# COEXPIX_connectors_schematics.net
KiCad netlist of a schematic drawn in Altium Designer
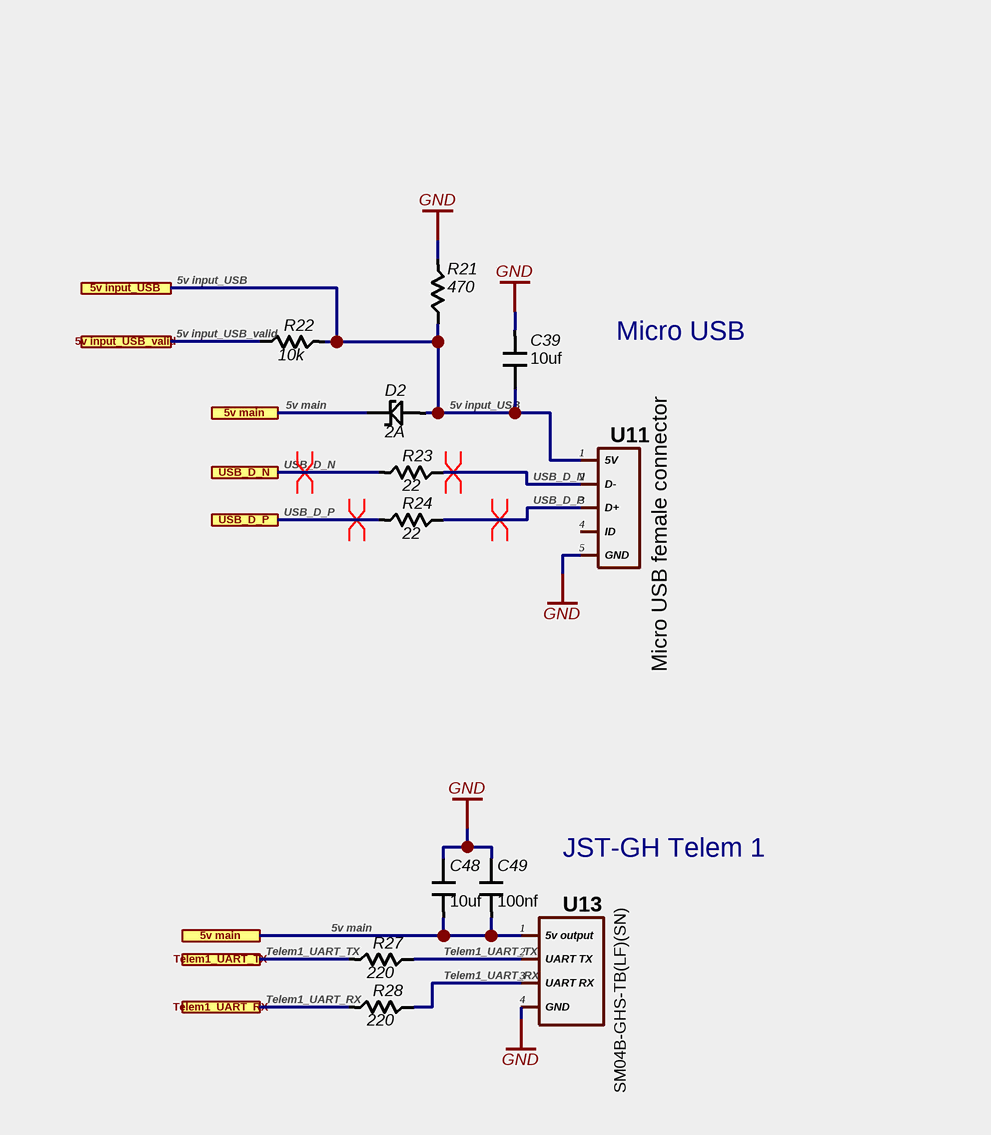
[diagram p0: COEXPIX connectors schematics.SchDoc, top left]
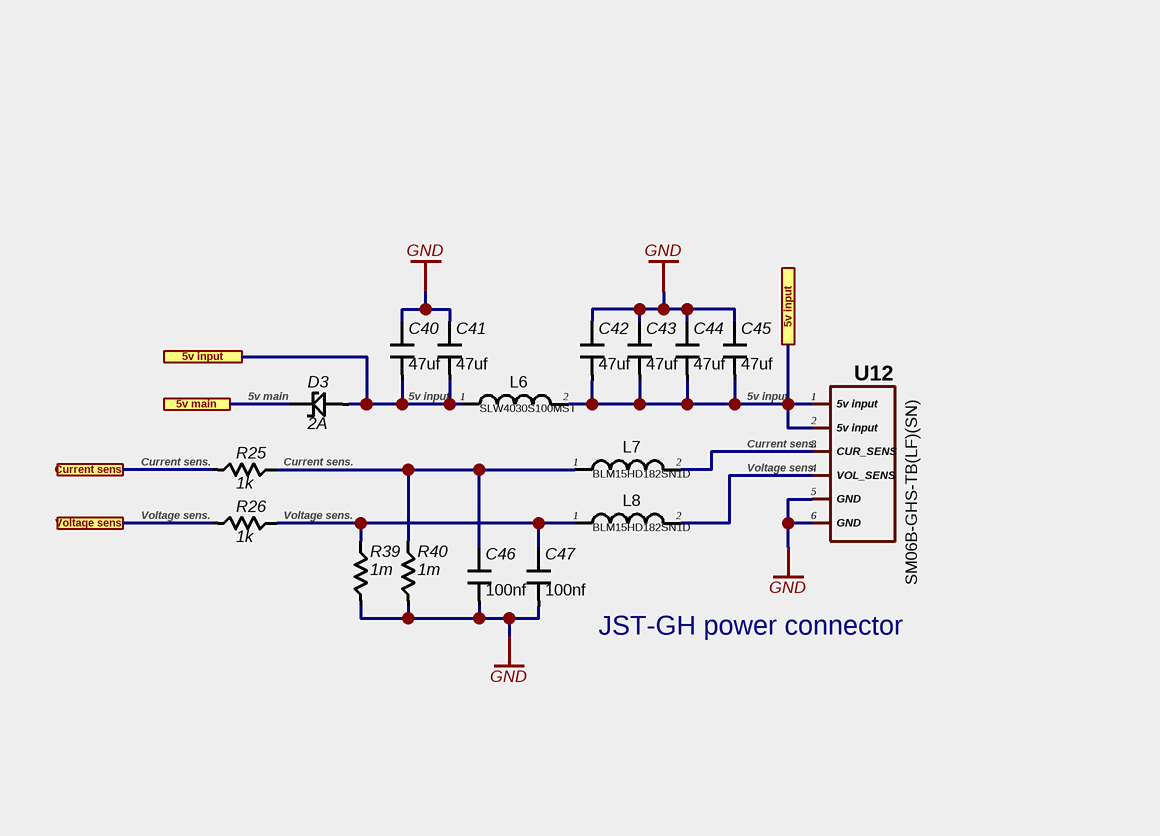
[diagram p1: COEXPIX connectors schematics.SchDoc, top right]
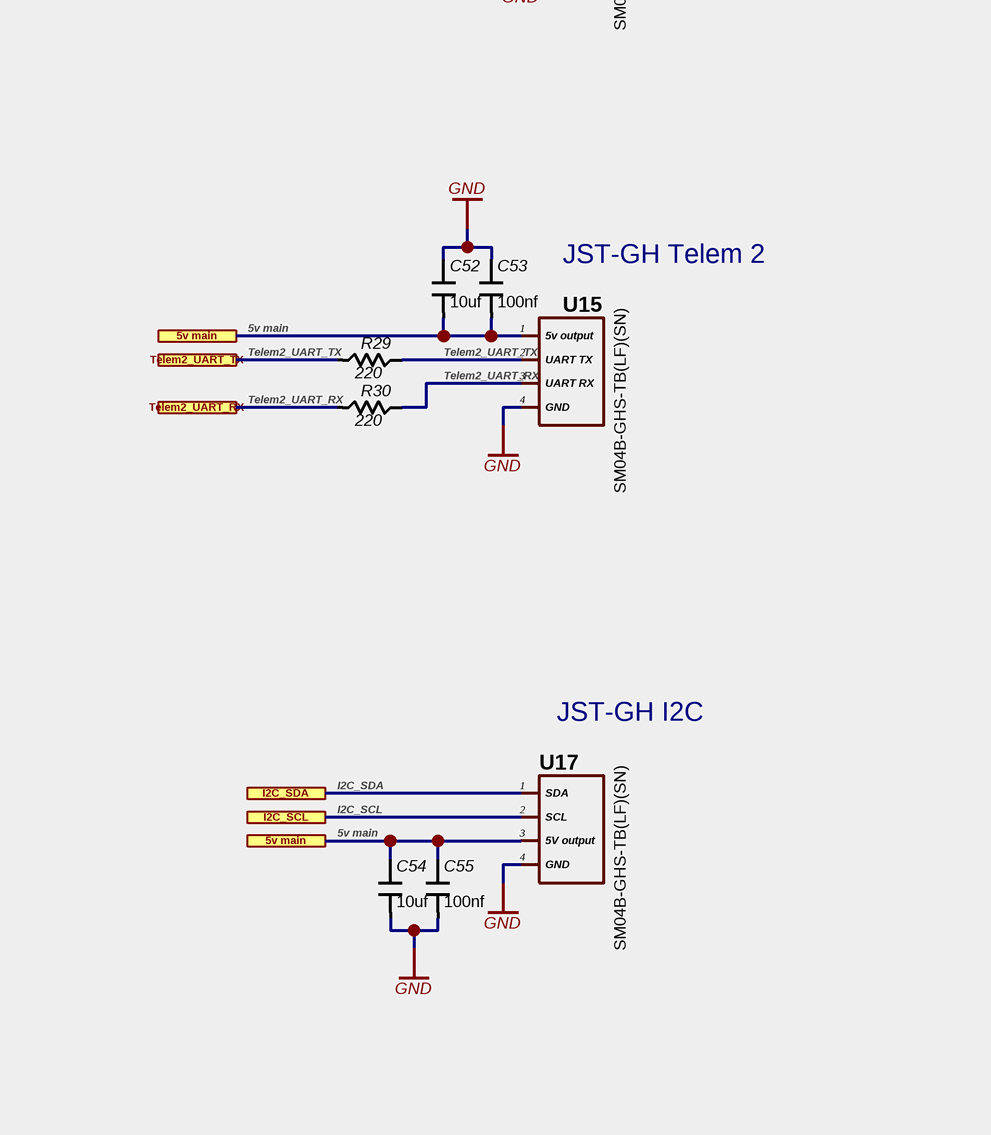
[diagram p2: COEXPIX connectors schematics.SchDoc, bottom left]
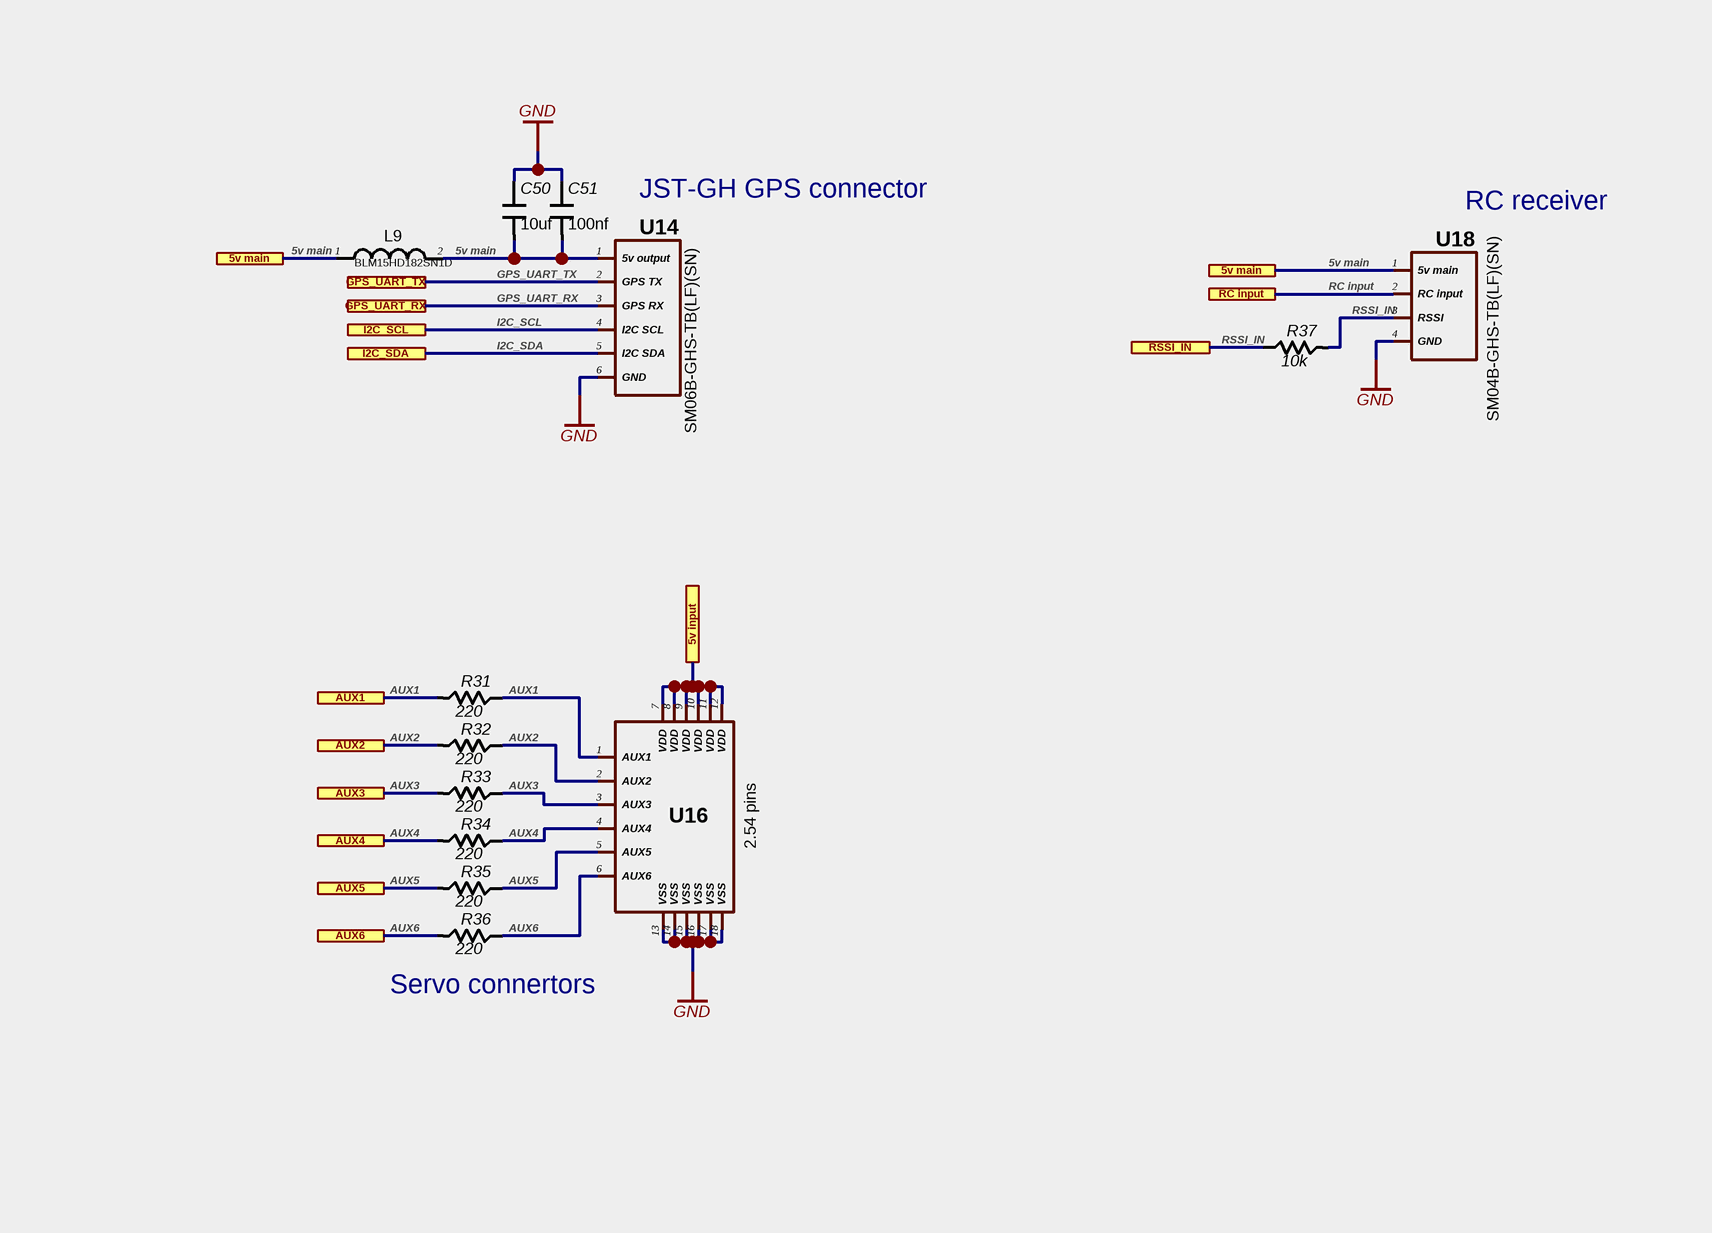
[diagram p3: COEXPIX connectors schematics.SchDoc, bottom right]

(export (version "E")
  (design (tool "Eeschema 10.0.6"))
  (components
    (comp (ref "C39")
      (value "10uf")
      (footprint "Capasitor 0402")
      (description "Multilayer Ceramic Capacitors MLCC - SMD/SMT 10uF 6.3V 0402")
      (fields (field (name "PART NUMBER") "JMK105CBJ106MV-F") (field (name "MANUFACTURER") "Taiyo Yuden"))
      (libsource (lib "Schematic symbols library") (part "Capacitor MLCC"))
    )
    (comp (ref "C40")
      (value "47uf")
      (footprint "Capasitor 0603")
      (description "Multilayer Ceramic Capacitors MLCC - SMD/SMT 47uF 6.3V 0603")
      (fields (field (name "PART NUMBER") "GRM188R60J476ME15D") (field (name "MANUFACTURER") "Murata"))
      (libsource (lib "Schematic symbols library") (part "Capacitor MLCC"))
    )
    (comp (ref "C41")
      (value "47uf")
      (footprint "Capasitor 0603")
      (description "Multilayer Ceramic Capacitors MLCC - SMD/SMT 47uF 6.3V 0603")
      (fields (field (name "PART NUMBER") "GRM188R60J476ME15D") (field (name "MANUFACTURER") "Murata"))
      (libsource (lib "Schematic symbols library") (part "Capacitor MLCC"))
    )
    (comp (ref "C42")
      (value "47uf")
      (footprint "Capasitor 0603")
      (description "Multilayer Ceramic Capacitors MLCC - SMD/SMT 47uF 6.3V 0603")
      (fields (field (name "PART NUMBER") "GRM188R60J476ME15D") (field (name "MANUFACTURER") "Murata"))
      (libsource (lib "Schematic symbols library") (part "Capacitor MLCC"))
    )
    (comp (ref "C43")
      (value "47uf")
      (footprint "Capasitor 0603")
      (description "Multilayer Ceramic Capacitors MLCC - SMD/SMT 47uF 6.3V 0603")
      (fields (field (name "PART NUMBER") "GRM188R60J476ME15D") (field (name "MANUFACTURER") "Murata"))
      (libsource (lib "Schematic symbols library") (part "Capacitor MLCC"))
    )
    (comp (ref "C44")
      (value "47uf")
      (footprint "Capasitor 0603")
      (description "Multilayer Ceramic Capacitors MLCC - SMD/SMT 47uF 6.3V 0603")
      (fields (field (name "PART NUMBER") "GRM188R60J476ME15D") (field (name "MANUFACTURER") "Murata"))
      (libsource (lib "Schematic symbols library") (part "Capacitor MLCC"))
    )
    (comp (ref "C45")
      (value "47uf")
      (footprint "Capasitor 0603")
      (description "Multilayer Ceramic Capacitors MLCC - SMD/SMT 47uF 6.3V 0603")
      (fields (field (name "PART NUMBER") "GRM188R60J476ME15D") (field (name "MANUFACTURER") "Murata"))
      (libsource (lib "Schematic symbols library") (part "Capacitor MLCC"))
    )
    (comp (ref "C46")
      (value "100nf")
      (footprint "Capasitor 0402")
      (description "Multilayer Ceramic Capacitors MLCC - SMD/SMT 100nF 16V 0402")
      (fields (field (name "PART NUMBER") "CC0402KRX7R7BB104") (field (name "MANUFACTURER") "YAGEO"))
      (libsource (lib "Schematic symbols library") (part "Capacitor MLCC"))
    )
    (comp (ref "C47")
      (value "100nf")
      (footprint "Capasitor 0402")
      (description "Multilayer Ceramic Capacitors MLCC - SMD/SMT 100nF 16V 0402")
      (fields (field (name "PART NUMBER") "CC0402KRX7R7BB104") (field (name "MANUFACTURER") "YAGEO"))
      (libsource (lib "Schematic symbols library") (part "Capacitor MLCC"))
    )
    (comp (ref "C48")
      (value "10uf")
      (footprint "Capasitor 0402")
      (description "Multilayer Ceramic Capacitors MLCC - SMD/SMT 10uF 6.3V 0402")
      (fields (field (name "PART NUMBER") "JMK105CBJ106MV-F") (field (name "MANUFACTURER") "Taiyo Yuden"))
      (libsource (lib "Schematic symbols library") (part "Capacitor MLCC"))
    )
    (comp (ref "C49")
      (value "100nf")
      (footprint "Capasitor 0402")
      (description "Multilayer Ceramic Capacitors MLCC - SMD/SMT 100nF 16V 0402")
      (fields (field (name "PART NUMBER") "CC0402KRX7R7BB104") (field (name "MANUFACTURER") "YAGEO"))
      (libsource (lib "Schematic symbols library") (part "Capacitor MLCC"))
    )
    (comp (ref "C50")
      (value "10uf")
      (footprint "Capasitor 0402")
      (description "Multilayer Ceramic Capacitors MLCC - SMD/SMT 10uF 6.3V 0402")
      (fields (field (name "PART NUMBER") "JMK105CBJ106MV-F") (field (name "MANUFACTURER") "Taiyo Yuden"))
      (libsource (lib "Schematic symbols library") (part "Capacitor MLCC"))
    )
    (comp (ref "C51")
      (value "100nf")
      (footprint "Capasitor 0402")
      (description "Multilayer Ceramic Capacitors MLCC - SMD/SMT 100nF 16V 0402")
      (fields (field (name "PART NUMBER") "CC0402KRX7R7BB104") (field (name "MANUFACTURER") "YAGEO"))
      (libsource (lib "Schematic symbols library") (part "Capacitor MLCC"))
    )
    (comp (ref "C52")
      (value "10uf")
      (footprint "Capasitor 0402")
      (description "Multilayer Ceramic Capacitors MLCC - SMD/SMT 10uF 6.3V 0402")
      (fields (field (name "PART NUMBER") "JMK105CBJ106MV-F") (field (name "MANUFACTURER") "Taiyo Yuden"))
      (libsource (lib "Schematic symbols library") (part "Capacitor MLCC"))
    )
    (comp (ref "C53")
      (value "100nf")
      (footprint "Capasitor 0402")
      (description "Multilayer Ceramic Capacitors MLCC - SMD/SMT 100nF 16V 0402")
      (fields (field (name "PART NUMBER") "CC0402KRX7R7BB104") (field (name "MANUFACTURER") "YAGEO"))
      (libsource (lib "Schematic symbols library") (part "Capacitor MLCC"))
    )
    (comp (ref "C54")
      (value "10uf")
      (footprint "Capasitor 0402")
      (description "Multilayer Ceramic Capacitors MLCC - SMD/SMT 10uF 6.3V 0402")
      (fields (field (name "PART NUMBER") "JMK105CBJ106MV-F") (field (name "MANUFACTURER") "Taiyo Yuden"))
      (libsource (lib "Schematic symbols library") (part "Capacitor MLCC"))
    )
    (comp (ref "C55")
      (value "100nf")
      (footprint "Capasitor 0402")
      (description "Multilayer Ceramic Capacitors MLCC - SMD/SMT 100nF 16V 0402")
      (fields (field (name "PART NUMBER") "CC0402KRX7R7BB104") (field (name "MANUFACTURER") "YAGEO"))
      (libsource (lib "Schematic symbols library") (part "Capacitor MLCC"))
    )
    (comp (ref "D2")
      (value "2A")
      (footprint "SOD-323F")
      (description "Schottky Barrier Diodes (SBD) SOD-323F")
      (fields (field (name "PART NUMBER") "SGP0230SD") (field (name "MANUFACTURER") "Suzhou Good-Ark Elec"))
      (libsource (lib "Schematic symbols library") (part "Schottky barrier diode"))
    )
    (comp (ref "D3")
      (value "2A")
      (footprint "SOD-323F")
      (description "Schottky Barrier Diodes (SBD) SOD-323F")
      (fields (field (name "PART NUMBER") "SGP0230SD") (field (name "MANUFACTURER") "Suzhou Good-Ark Elec"))
      (libsource (lib "Schematic symbols library") (part "Schottky barrier diode"))
    )
    (comp (ref "L6")
      (value "SLW4030S100MST")
      (footprint "Inductor 4030")
      (description "Power Inductors 10uH ±20% 1.5A SMD,4x4x3mm")
      (fields (field (name "MANUFACTURER") "Sunltech Tech"))
      (libsource (lib "Schematic symbols library") (part "FB / Inductor"))
    )
    (comp (ref "L7")
      (value "BLM15HD182SN1D")
      (footprint "Ferrite bead 0402")
      (description "Beads 0402")
      (fields (field (name "MANUFACTURER") "Murata Electronics"))
      (libsource (lib "Schematic symbols library") (part "FB / Inductor"))
    )
    (comp (ref "L8")
      (value "BLM15HD182SN1D")
      (footprint "Ferrite bead 0402")
      (description "Beads 0402")
      (fields (field (name "MANUFACTURER") "Murata Electronics"))
      (libsource (lib "Schematic symbols library") (part "FB / Inductor"))
    )
    (comp (ref "L9")
      (value "BLM15HD182SN1D")
      (footprint "Ferrite bead 0402")
      (description "Beads 0402")
      (fields (field (name "MANUFACTURER") "Murata Electronics"))
      (libsource (lib "Schematic symbols library") (part "FB / Inductor"))
    )
    (comp (ref "R21")
      (value "470")
      (footprint "Resistor 0402")
      (description "Chip Resistor - Surface Mount 470Ohms ±1% 1/16W 0402")
      (fields (field (name "PART NUMBER") "RC0402FR-07470RL") (field (name "MANUFACTURER") "YAGEO"))
      (libsource (lib "Schematic symbols library") (part "Resistor"))
    )
    (comp (ref "R22")
      (value "10k")
      (footprint "Resistor 0402")
      (description "Chip Resistor - Surface Mount 10KOhms ±1% 1/16W 0402")
      (fields (field (name "PART NUMBER") "RC0402FR-0710KL") (field (name "MANUFACTURER") "YAGEO"))
      (libsource (lib "Schematic symbols library") (part "Resistor"))
    )
    (comp (ref "R23")
      (value "22")
      (footprint "Resistor 0402")
      (description "Chip Resistor - Surface Mount 22Ohms ±1% 1/16W 0402")
      (fields (field (name "PART NUMBER") "RC0402FR-0722RL") (field (name "MANUFACTURER") "YAGEO"))
      (libsource (lib "Schematic symbols library") (part "Resistor"))
    )
    (comp (ref "R24")
      (value "22")
      (footprint "Resistor 0402")
      (description "Chip Resistor - Surface Mount 22Ohms ±1% 1/16W 0402")
      (fields (field (name "PART NUMBER") "RC0402FR-0722RL") (field (name "MANUFACTURER") "YAGEO"))
      (libsource (lib "Schematic symbols library") (part "Resistor"))
    )
    (comp (ref "R25")
      (value "1k")
      (footprint "Resistor 0402")
      (description "Chip Resistor - Surface Mount 1KOhms ±1% 1/16W 0402")
      (fields (field (name "PART NUMBER") "RC0402FR-071KL") (field (name "MANUFACTURER") "YAGEO"))
      (libsource (lib "Schematic symbols library") (part "Resistor"))
    )
    (comp (ref "R26")
      (value "1k")
      (footprint "Resistor 0402")
      (description "Chip Resistor - Surface Mount 1KOhms ±1% 1/16W 0402")
      (fields (field (name "PART NUMBER") "RC0402FR-071KL") (field (name "MANUFACTURER") "YAGEO"))
      (libsource (lib "Schematic symbols library") (part "Resistor"))
    )
    (comp (ref "R27")
      (value "220")
      (footprint "Resistor 0402")
      (description "Chip Resistor - Surface Mount 220Ohms ±1% 1/16W 040")
      (fields (field (name "PART NUMBER") "0402WGF2200TCE") (field (name "MANUFACTURER") "Uniroyal Elec"))
      (libsource (lib "Schematic symbols library") (part "Resistor"))
    )
    (comp (ref "R28")
      (value "220")
      (footprint "Resistor 0402")
      (description "Chip Resistor - Surface Mount 220Ohms ±1% 1/16W 040")
      (fields (field (name "PART NUMBER") "0402WGF2200TCE") (field (name "MANUFACTURER") "Uniroyal Elec"))
      (libsource (lib "Schematic symbols library") (part "Resistor"))
    )
    (comp (ref "R29")
      (value "220")
      (footprint "Resistor 0402")
      (description "Chip Resistor - Surface Mount 220Ohms ±1% 1/16W 040")
      (fields (field (name "PART NUMBER") "0402WGF2200TCE") (field (name "MANUFACTURER") "Uniroyal Elec"))
      (libsource (lib "Schematic symbols library") (part "Resistor"))
    )
    (comp (ref "R30")
      (value "220")
      (footprint "Resistor 0402")
      (description "Chip Resistor - Surface Mount 220Ohms ±1% 1/16W 040")
      (fields (field (name "PART NUMBER") "0402WGF2200TCE") (field (name "MANUFACTURER") "Uniroyal Elec"))
      (libsource (lib "Schematic symbols library") (part "Resistor"))
    )
    (comp (ref "R31")
      (value "220")
      (footprint "Resistor 0402")
      (description "Chip Resistor - Surface Mount 220Ohms ±1% 1/16W 040")
      (fields (field (name "PART NUMBER") "0402WGF2200TCE") (field (name "MANUFACTURER") "Uniroyal Elec"))
      (libsource (lib "Schematic symbols library") (part "Resistor"))
    )
    (comp (ref "R32")
      (value "220")
      (footprint "Resistor 0402")
      (description "Chip Resistor - Surface Mount 220Ohms ±1% 1/16W 040")
      (fields (field (name "PART NUMBER") "0402WGF2200TCE") (field (name "MANUFACTURER") "Uniroyal Elec"))
      (libsource (lib "Schematic symbols library") (part "Resistor"))
    )
    (comp (ref "R33")
      (value "220")
      (footprint "Resistor 0402")
      (description "Chip Resistor - Surface Mount 220Ohms ±1% 1/16W 040")
      (fields (field (name "PART NUMBER") "0402WGF2200TCE") (field (name "MANUFACTURER") "Uniroyal Elec"))
      (libsource (lib "Schematic symbols library") (part "Resistor"))
    )
    (comp (ref "R34")
      (value "220")
      (footprint "Resistor 0402")
      (description "Chip Resistor - Surface Mount 220Ohms ±1% 1/16W 040")
      (fields (field (name "PART NUMBER") "0402WGF2200TCE") (field (name "MANUFACTURER") "Uniroyal Elec"))
      (libsource (lib "Schematic symbols library") (part "Resistor"))
    )
    (comp (ref "R35")
      (value "220")
      (footprint "Resistor 0402")
      (description "Chip Resistor - Surface Mount 220Ohms ±1% 1/16W 040")
      (fields (field (name "PART NUMBER") "0402WGF2200TCE") (field (name "MANUFACTURER") "Uniroyal Elec"))
      (libsource (lib "Schematic symbols library") (part "Resistor"))
    )
    (comp (ref "R36")
      (value "220")
      (footprint "Resistor 0402")
      (description "Chip Resistor - Surface Mount 220Ohms ±1% 1/16W 040")
      (fields (field (name "PART NUMBER") "0402WGF2200TCE") (field (name "MANUFACTURER") "Uniroyal Elec"))
      (libsource (lib "Schematic symbols library") (part "Resistor"))
    )
    (comp (ref "R37")
      (value "10k")
      (footprint "Resistor 0402")
      (description "Chip Resistor - Surface Mount 10KOhms ±1% 1/16W 0402")
      (fields (field (name "PART NUMBER") "RC0402FR-0710KL") (field (name "MANUFACTURER") "YAGEO"))
      (libsource (lib "Schematic symbols library") (part "Resistor"))
    )
    (comp (ref "R39")
      (value "1m")
      (footprint "Resistor 0402")
      (description "1M ±1% 1/16W ±100ppm/°C 0402 Chip Resistor")
      (fields (field (name "PART NUMBER") "WR04X1004FTL") (field (name "MANUFACTURER") "Walsin Tech Corp"))
      (libsource (lib "Schematic symbols library") (part "Resistor"))
    )
    (comp (ref "R40")
      (value "1m")
      (footprint "Resistor 0402")
      (description "1M ±1% 1/16W ±100ppm/°C 0402 Chip Resistor")
      (fields (field (name "PART NUMBER") "WR04X1004FTL") (field (name "MANUFACTURER") "Walsin Tech Corp"))
      (libsource (lib "Schematic symbols library") (part "Resistor"))
    )
    (comp (ref "U11")
      (value "Micro USB female connector")
      (footprint "MicroUSB THREW HOLES")
      (description "USB Connectors SMD")
      (fields (field (name "MANUFACTURER") "Jing Extension of the Electronic Co."))
      (libsource (lib "Schematic symbols library") (part "Micro USB"))
    )
    (comp (ref "U12")
      (value "SM06B-GHS-TB(LF)(SN)")
      (footprint "JST-GH 6 PIN")
      (description "Wire To Board / Wire To Wire Connector SMD")
      (fields (field (name "MANUFACTURER") "JST Sales America"))
      (libsource (lib "Schematic symbols library") (part "JST-GH 6"))
    )
    (comp (ref "U13")
      (value "SM04B-GHS-TB(LF)(SN)")
      (footprint "JST-GH 4 pin")
      (description "Wire To Board / Wire To Wire Connector socket P=1.25mm")
      (fields (field (name "MANUFACTURER") "JST Sales America"))
      (libsource (lib "Schematic symbols library") (part "JST-GH 4"))
    )
    (comp (ref "U14")
      (value "SM06B-GHS-TB(LF)(SN)")
      (footprint "JST-GH 6 PIN")
      (description "Wire To Board / Wire To Wire Connector SMD")
      (fields (field (name "MANUFACTURER") "JST Sales America"))
      (libsource (lib "Schematic symbols library") (part "JST-GH 6"))
    )
    (comp (ref "U15")
      (value "SM04B-GHS-TB(LF)(SN)")
      (footprint "JST-GH 4 pin")
      (description "Wire To Board / Wire To Wire Connector socket P=1.25mm")
      (fields (field (name "MANUFACTURER") "JST Sales America"))
      (libsource (lib "Schematic symbols library") (part "JST-GH 4"))
    )
    (comp (ref "U16")
      (value "2.54 pins")
      (footprint "3x6 PX4 servo array")
      (fields (field (name "PART NUMBER") "2.54 pins array"))
      (libsource (lib "Schematic symbols library") (part "3x6 dupont pins"))
    )
    (comp (ref "U17")
      (value "SM04B-GHS-TB(LF)(SN)")
      (footprint "JST-GH 4 pin")
      (description "Wire To Board / Wire To Wire Connector socket P=1.25mm")
      (fields (field (name "MANUFACTURER") "JST Sales America"))
      (libsource (lib "Schematic symbols library") (part "JST-GH 4"))
    )
    (comp (ref "U18")
      (value "SM04B-GHS-TB(LF)(SN)")
      (footprint "JST-GH 4 pin")
      (description "Wire To Board / Wire To Wire Connector socket P=1.25mm")
      (fields (field (name "MANUFACTURER") "JST Sales America"))
      (libsource (lib "Schematic symbols library") (part "JST-GH 4"))
    )
  )
  (nets
    (net (code "1") (name "/5v input") (class "Default")
      (node (ref "C40") (pin "2") (pinfunction "2_2") (pintype "passive"))
      (node (ref "C41") (pin "2") (pinfunction "2_2") (pintype "passive"))
      (node (ref "C42") (pin "2") (pinfunction "2_2") (pintype "passive"))
      (node (ref "C43") (pin "2") (pinfunction "2_2") (pintype "passive"))
      (node (ref "C44") (pin "2") (pinfunction "2_2") (pintype "passive"))
      (node (ref "C45") (pin "2") (pinfunction "2_2") (pintype "passive"))
      (node (ref "D3") (pin "2") (pinfunction "2_2") (pintype "passive"))
      (node (ref "L6") (pin "1") (pintype "power_in"))
      (node (ref "L6") (pin "2") (pintype "power_in"))
      (node (ref "U12") (pin "1") (pinfunction "5v_output_1") (pintype "power_in"))
      (node (ref "U12") (pin "2") (pinfunction "GPS_TX_2") (pintype "power_in"))
      (node (ref "U16") (pin "10") (pinfunction "VDD_10") (pintype "power_in"))
      (node (ref "U16") (pin "11") (pinfunction "VDD_11") (pintype "power_in"))
      (node (ref "U16") (pin "12") (pinfunction "VDD_12") (pintype "power_in"))
      (node (ref "U16") (pin "7") (pinfunction "VDD_7") (pintype "power_in"))
      (node (ref "U16") (pin "8") (pinfunction "VDD_8") (pintype "power_in"))
      (node (ref "U16") (pin "9") (pinfunction "VDD_9") (pintype "power_in"))
    )
    (net (code "2") (name "/5v input_USB") (class "Default")
      (node (ref "C39") (pin "1") (pinfunction "1_1") (pintype "passive"))
      (node (ref "D2") (pin "2") (pinfunction "2_2") (pintype "passive"))
      (node (ref "R21") (pin "1") (pinfunction "1_1") (pintype "passive"))
      (node (ref "R22") (pin "2") (pinfunction "2_2") (pintype "passive"))
      (node (ref "U11") (pin "1") (pinfunction "5V_1") (pintype "power_in"))
    )
    (net (code "3") (name "/5v input_USB_valid") (class "Default")
      (node (ref "R22") (pin "1") (pinfunction "1_1") (pintype "passive"))
    )
    (net (code "4") (name "/5v main") (class "Default")
      (node (ref "C48") (pin "2") (pinfunction "2_2") (pintype "passive"))
      (node (ref "C49") (pin "2") (pinfunction "2_2") (pintype "passive"))
      (node (ref "C50") (pin "2") (pinfunction "2_2") (pintype "passive"))
      (node (ref "C51") (pin "2") (pinfunction "2_2") (pintype "passive"))
      (node (ref "C52") (pin "2") (pinfunction "2_2") (pintype "passive"))
      (node (ref "C53") (pin "2") (pinfunction "2_2") (pintype "passive"))
      (node (ref "C54") (pin "1") (pinfunction "1_1") (pintype "passive"))
      (node (ref "C55") (pin "1") (pinfunction "1_1") (pintype "passive"))
      (node (ref "D2") (pin "1") (pinfunction "1_1") (pintype "passive"))
      (node (ref "D3") (pin "1") (pinfunction "1_1") (pintype "passive"))
      (node (ref "L9") (pin "1") (pintype "power_in"))
      (node (ref "L9") (pin "2") (pintype "power_in"))
      (node (ref "U13") (pin "1") (pinfunction "5v_main_1") (pintype "power_in"))
      (node (ref "U14") (pin "1") (pinfunction "5v_output_1") (pintype "power_in"))
      (node (ref "U15") (pin "1") (pinfunction "5v_main_1") (pintype "power_in"))
      (node (ref "U17") (pin "3") (pinfunction "RSSI_3") (pintype "power_in"))
      (node (ref "U18") (pin "1") (pinfunction "5v_main_1") (pintype "power_in"))
    )
    (net (code "5") (name "/AUX1") (class "Default")
      (node (ref "R31") (pin "1") (pinfunction "1_1") (pintype "passive"))
      (node (ref "R31") (pin "2") (pinfunction "2_2") (pintype "passive"))
      (node (ref "U16") (pin "1") (pinfunction "AUX1_1") (pintype "power_in"))
    )
    (net (code "6") (name "/AUX2") (class "Default")
      (node (ref "R32") (pin "1") (pinfunction "1_1") (pintype "passive"))
      (node (ref "R32") (pin "2") (pinfunction "2_2") (pintype "passive"))
      (node (ref "U16") (pin "2") (pinfunction "AUX2_2") (pintype "power_in"))
    )
    (net (code "7") (name "/AUX3") (class "Default")
      (node (ref "R33") (pin "1") (pinfunction "1_1") (pintype "passive"))
      (node (ref "R33") (pin "2") (pinfunction "2_2") (pintype "passive"))
      (node (ref "U16") (pin "3") (pinfunction "AUX3_3") (pintype "power_in"))
    )
    (net (code "8") (name "/AUX4") (class "Default")
      (node (ref "R34") (pin "1") (pinfunction "1_1") (pintype "passive"))
      (node (ref "R34") (pin "2") (pinfunction "2_2") (pintype "passive"))
      (node (ref "U16") (pin "4") (pinfunction "AUX4_4") (pintype "power_in"))
    )
    (net (code "9") (name "/AUX5") (class "Default")
      (node (ref "R35") (pin "1") (pinfunction "1_1") (pintype "passive"))
      (node (ref "R35") (pin "2") (pinfunction "2_2") (pintype "passive"))
      (node (ref "U16") (pin "5") (pinfunction "AUX5_5") (pintype "power_in"))
    )
    (net (code "10") (name "/AUX6") (class "Default")
      (node (ref "R36") (pin "1") (pinfunction "1_1") (pintype "passive"))
      (node (ref "R36") (pin "2") (pinfunction "2_2") (pintype "passive"))
      (node (ref "U16") (pin "6") (pinfunction "AUX6_6") (pintype "power_in"))
    )
    (net (code "11") (name "/Current sens.") (class "Default")
      (node (ref "C46") (pin "1") (pinfunction "1_1") (pintype "passive"))
      (node (ref "L7") (pin "1") (pintype "power_in"))
      (node (ref "L7") (pin "2") (pintype "power_in"))
      (node (ref "R25") (pin "1") (pinfunction "1_1") (pintype "passive"))
      (node (ref "R25") (pin "2") (pinfunction "2_2") (pintype "passive"))
      (node (ref "R40") (pin "1") (pinfunction "1_1") (pintype "passive"))
      (node (ref "U12") (pin "3") (pinfunction "GPS_RX_3") (pintype "power_in"))
    )
    (net (code "12") (name "/GPS_UART_RX") (class "Default")
      (node (ref "U14") (pin "3") (pinfunction "GPS_RX_3") (pintype "power_in"))
    )
    (net (code "13") (name "/GPS_UART_TX") (class "Default")
      (node (ref "U14") (pin "2") (pinfunction "GPS_TX_2") (pintype "power_in"))
    )
    (net (code "14") (name "/I2C_SCL") (class "Default")
      (node (ref "U14") (pin "4") (pinfunction "I2C_SCL_4") (pintype "power_in"))
      (node (ref "U17") (pin "2") (pinfunction "RC_input_2") (pintype "power_in"))
    )
    (net (code "15") (name "/I2C_SDA") (class "Default")
      (node (ref "U14") (pin "5") (pinfunction "I2C_SDA_5") (pintype "power_in"))
      (node (ref "U17") (pin "1") (pinfunction "5v_main_1") (pintype "power_in"))
    )
    (net (code "16") (name "/RC input") (class "Default")
      (node (ref "U18") (pin "2") (pinfunction "RC_input_2") (pintype "power_in"))
    )
    (net (code "17") (name "/RSSI_IN") (class "Default")
      (node (ref "R37") (pin "1") (pinfunction "1_1") (pintype "passive"))
      (node (ref "R37") (pin "2") (pinfunction "2_2") (pintype "passive"))
      (node (ref "U18") (pin "3") (pinfunction "RSSI_3") (pintype "power_in"))
    )
    (net (code "18") (name "/Telem1_UART_RX") (class "Default")
      (node (ref "R28") (pin "1") (pinfunction "1_1") (pintype "passive"))
      (node (ref "R28") (pin "2") (pinfunction "2_2") (pintype "passive"))
      (node (ref "U13") (pin "3") (pinfunction "RSSI_3") (pintype "power_in"))
    )
    (net (code "19") (name "/Telem1_UART_TX") (class "Default")
      (node (ref "R27") (pin "1") (pinfunction "1_1") (pintype "passive"))
      (node (ref "R27") (pin "2") (pinfunction "2_2") (pintype "passive"))
      (node (ref "U13") (pin "2") (pinfunction "RC_input_2") (pintype "power_in"))
    )
    (net (code "20") (name "/Telem2_UART_RX") (class "Default")
      (node (ref "R30") (pin "1") (pinfunction "1_1") (pintype "passive"))
      (node (ref "R30") (pin "2") (pinfunction "2_2") (pintype "passive"))
      (node (ref "U15") (pin "3") (pinfunction "RSSI_3") (pintype "power_in"))
    )
    (net (code "21") (name "/Telem2_UART_TX") (class "Default")
      (node (ref "R29") (pin "1") (pinfunction "1_1") (pintype "passive"))
      (node (ref "R29") (pin "2") (pinfunction "2_2") (pintype "passive"))
      (node (ref "U15") (pin "2") (pinfunction "RC_input_2") (pintype "power_in"))
    )
    (net (code "22") (name "/USB_D_N") (class "Default")
      (node (ref "R23") (pin "1") (pinfunction "1_1") (pintype "passive"))
      (node (ref "R23") (pin "2") (pinfunction "2_2") (pintype "passive"))
      (node (ref "U11") (pin "2") (pinfunction "D-_2") (pintype "power_in"))
    )
    (net (code "23") (name "/USB_D_P") (class "Default")
      (node (ref "R24") (pin "1") (pinfunction "1_1") (pintype "passive"))
      (node (ref "R24") (pin "2") (pinfunction "2_2") (pintype "passive"))
      (node (ref "U11") (pin "3") (pinfunction "D+_3") (pintype "power_in"))
    )
    (net (code "24") (name "/Voltage sens.") (class "Default")
      (node (ref "C47") (pin "1") (pinfunction "1_1") (pintype "passive"))
      (node (ref "L8") (pin "1") (pintype "power_in"))
      (node (ref "L8") (pin "2") (pintype "power_in"))
      (node (ref "R26") (pin "1") (pinfunction "1_1") (pintype "passive"))
      (node (ref "R26") (pin "2") (pinfunction "2_2") (pintype "passive"))
      (node (ref "R39") (pin "1") (pinfunction "1_1") (pintype "passive"))
      (node (ref "U12") (pin "4") (pinfunction "I2C_SCL_4") (pintype "power_in"))
    )
    (net (code "25") (name "GND") (class "Default")
      (node (ref "C39") (pin "2") (pinfunction "2_2") (pintype "passive"))
      (node (ref "C40") (pin "1") (pinfunction "1_1") (pintype "passive"))
      (node (ref "C41") (pin "1") (pinfunction "1_1") (pintype "passive"))
      (node (ref "C42") (pin "1") (pinfunction "1_1") (pintype "passive"))
      (node (ref "C43") (pin "1") (pinfunction "1_1") (pintype "passive"))
      (node (ref "C44") (pin "1") (pinfunction "1_1") (pintype "passive"))
      (node (ref "C45") (pin "1") (pinfunction "1_1") (pintype "passive"))
      (node (ref "C46") (pin "2") (pinfunction "2_2") (pintype "passive"))
      (node (ref "C47") (pin "2") (pinfunction "2_2") (pintype "passive"))
      (node (ref "C48") (pin "1") (pinfunction "1_1") (pintype "passive"))
      (node (ref "C49") (pin "1") (pinfunction "1_1") (pintype "passive"))
      (node (ref "C50") (pin "1") (pinfunction "1_1") (pintype "passive"))
      (node (ref "C51") (pin "1") (pinfunction "1_1") (pintype "passive"))
      (node (ref "C52") (pin "1") (pinfunction "1_1") (pintype "passive"))
      (node (ref "C53") (pin "1") (pinfunction "1_1") (pintype "passive"))
      (node (ref "C54") (pin "2") (pinfunction "2_2") (pintype "passive"))
      (node (ref "C55") (pin "2") (pinfunction "2_2") (pintype "passive"))
      (node (ref "R21") (pin "2") (pinfunction "2_2") (pintype "passive"))
      (node (ref "R39") (pin "2") (pinfunction "2_2") (pintype "passive"))
      (node (ref "R40") (pin "2") (pinfunction "2_2") (pintype "passive"))
      (node (ref "U11") (pin "5") (pinfunction "GND_5") (pintype "power_in"))
      (node (ref "U12") (pin "5") (pinfunction "I2C_SDA_5") (pintype "power_in"))
      (node (ref "U12") (pin "6") (pinfunction "GND_6") (pintype "power_in"))
      (node (ref "U13") (pin "4") (pinfunction "GND_4") (pintype "power_in"))
      (node (ref "U14") (pin "6") (pinfunction "GND_6") (pintype "power_in"))
      (node (ref "U15") (pin "4") (pinfunction "GND_4") (pintype "power_in"))
      (node (ref "U16") (pin "13") (pinfunction "VSS_13") (pintype "power_in"))
      (node (ref "U16") (pin "14") (pinfunction "VSS_14") (pintype "power_in"))
      (node (ref "U16") (pin "15") (pinfunction "VSS_15") (pintype "power_in"))
      (node (ref "U16") (pin "16") (pinfunction "VSS_16") (pintype "power_in"))
      (node (ref "U16") (pin "17") (pinfunction "VSS_17") (pintype "power_in"))
      (node (ref "U16") (pin "18") (pinfunction "VSS_18") (pintype "power_in"))
      (node (ref "U17") (pin "4") (pinfunction "GND_4") (pintype "power_in"))
      (node (ref "U18") (pin "4") (pinfunction "GND_4") (pintype "power_in"))
    )
    (net (code "26") (name "unconnected-(U11-ID-Pad4)") (class "Default")
      (node (ref "U11") (pin "4") (pinfunction "ID_4") (pintype "power_in"))
    )
  )
)
